# v2.net
KiCad netlist of a schematic drawn in Altium Designer
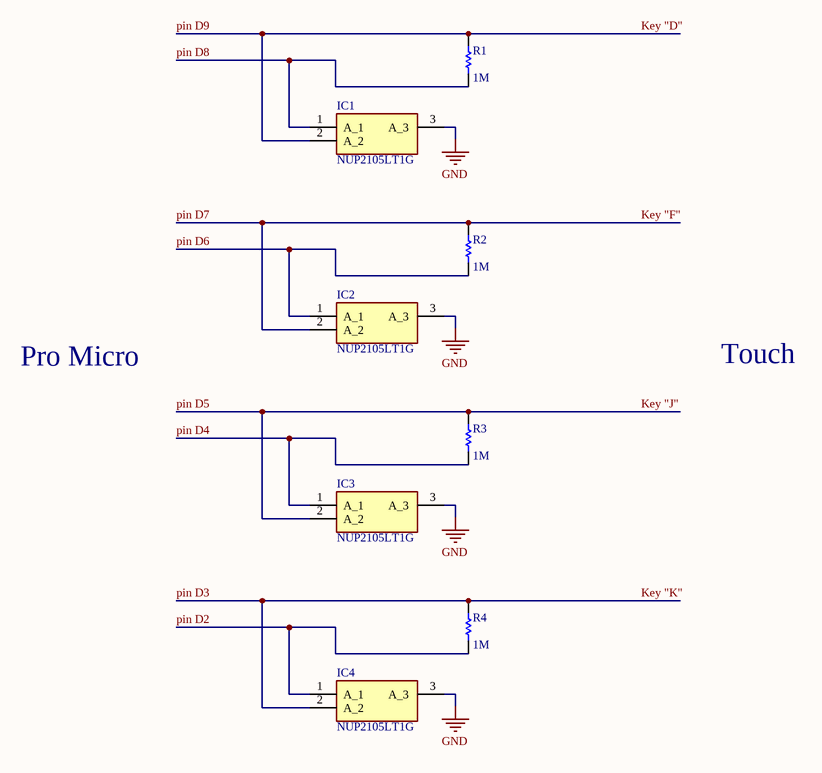
[diagram p0: v2.SchDoc]

(export (version "E")
  (design (tool "Eeschema 10.0.6"))
  (components
    (comp (ref "IC1")
      (value "NUP2105LT1G")
      (footprint "SamacSys:SOT96P237X111-3N")
      (description "Integrated Circuit")
      (fields (field (name "MOUSER PART NUMBER") "863-NUP2105LT1G"))
      (libsource (lib "*") (part "NUP2105LT1G"))
    )
    (comp (ref "IC2")
      (value "NUP2105LT1G")
      (footprint "SamacSys:SOT96P237X111-3N")
      (description "Integrated Circuit")
      (fields (field (name "MOUSER PART NUMBER") "863-NUP2105LT1G"))
      (libsource (lib "*") (part "NUP2105LT1G"))
    )
    (comp (ref "IC3")
      (value "NUP2105LT1G")
      (footprint "SamacSys:SOT96P237X111-3N")
      (description "Integrated Circuit")
      (fields (field (name "MOUSER PART NUMBER") "863-NUP2105LT1G"))
      (libsource (lib "*") (part "NUP2105LT1G"))
    )
    (comp (ref "IC4")
      (value "NUP2105LT1G")
      (footprint "SamacSys:SOT96P237X111-3N")
      (description "Integrated Circuit")
      (fields (field (name "MOUSER PART NUMBER") "863-NUP2105LT1G"))
      (libsource (lib "*") (part "NUP2105LT1G"))
    )
    (comp (ref "R1")
      (value "1M")
      (footprint "AXIAL-0.3")
      (description "Resistor")
      (fields (field (name "Comment") "Res1") (field (name "PUBLISHER") "Altium Limited"))
      (libsource (lib "Miscellaneous Devices") (part "Res1"))
    )
    (comp (ref "R2")
      (value "1M")
      (footprint "AXIAL-0.3")
      (description "Resistor")
      (fields (field (name "Comment") "Res1") (field (name "PUBLISHER") "Altium Limited"))
      (libsource (lib "Miscellaneous Devices") (part "Res1"))
    )
    (comp (ref "R3")
      (value "1M")
      (footprint "AXIAL-0.3")
      (description "Resistor")
      (fields (field (name "Comment") "Res1") (field (name "PUBLISHER") "Altium Limited"))
      (libsource (lib "Miscellaneous Devices") (part "Res1"))
    )
    (comp (ref "R4")
      (value "1M")
      (footprint "AXIAL-0.3")
      (description "Resistor")
      (fields (field (name "Comment") "Res1") (field (name "PUBLISHER") "Altium Limited"))
      (libsource (lib "Miscellaneous Devices") (part "Res1"))
    )
  )
  (nets
    (net (code "1") (name "/Key \"D\"") (class "Default")
      (node (ref "IC1") (pin "2") (pinfunction "A_2_2") (pintype "passive"))
      (node (ref "R1") (pin "2") (pinfunction "2_2") (pintype "passive"))
    )
    (net (code "2") (name "/Key \"F\"") (class "Default")
      (node (ref "IC2") (pin "2") (pinfunction "A_2_2") (pintype "passive"))
      (node (ref "R2") (pin "2") (pinfunction "2_2") (pintype "passive"))
    )
    (net (code "3") (name "/Key \"J\"") (class "Default")
      (node (ref "IC3") (pin "2") (pinfunction "A_2_2") (pintype "passive"))
      (node (ref "R3") (pin "2") (pinfunction "2_2") (pintype "passive"))
    )
    (net (code "4") (name "/Key \"K\"") (class "Default")
      (node (ref "IC4") (pin "2") (pinfunction "A_2_2") (pintype "passive"))
      (node (ref "R4") (pin "2") (pinfunction "2_2") (pintype "passive"))
    )
    (net (code "5") (name "/pin D2") (class "Default")
      (node (ref "IC4") (pin "1") (pinfunction "A_1_1") (pintype "passive"))
      (node (ref "R4") (pin "1") (pinfunction "1_1") (pintype "passive"))
    )
    (net (code "6") (name "/pin D4") (class "Default")
      (node (ref "IC3") (pin "1") (pinfunction "A_1_1") (pintype "passive"))
      (node (ref "R3") (pin "1") (pinfunction "1_1") (pintype "passive"))
    )
    (net (code "7") (name "/pin D6") (class "Default")
      (node (ref "IC2") (pin "1") (pinfunction "A_1_1") (pintype "passive"))
      (node (ref "R2") (pin "1") (pinfunction "1_1") (pintype "passive"))
    )
    (net (code "8") (name "/pin D8") (class "Default")
      (node (ref "IC1") (pin "1") (pinfunction "A_1_1") (pintype "passive"))
      (node (ref "R1") (pin "1") (pinfunction "1_1") (pintype "passive"))
    )
    (net (code "9") (name "GND") (class "Default")
      (node (ref "IC1") (pin "3") (pinfunction "A_3_3") (pintype "passive"))
      (node (ref "IC2") (pin "3") (pinfunction "A_3_3") (pintype "passive"))
      (node (ref "IC3") (pin "3") (pinfunction "A_3_3") (pintype "passive"))
      (node (ref "IC4") (pin "3") (pinfunction "A_3_3") (pintype "passive"))
    )
  )
)
